# JTAG_Configuration.net
KiCad netlist of a schematic drawn in Altium Designer
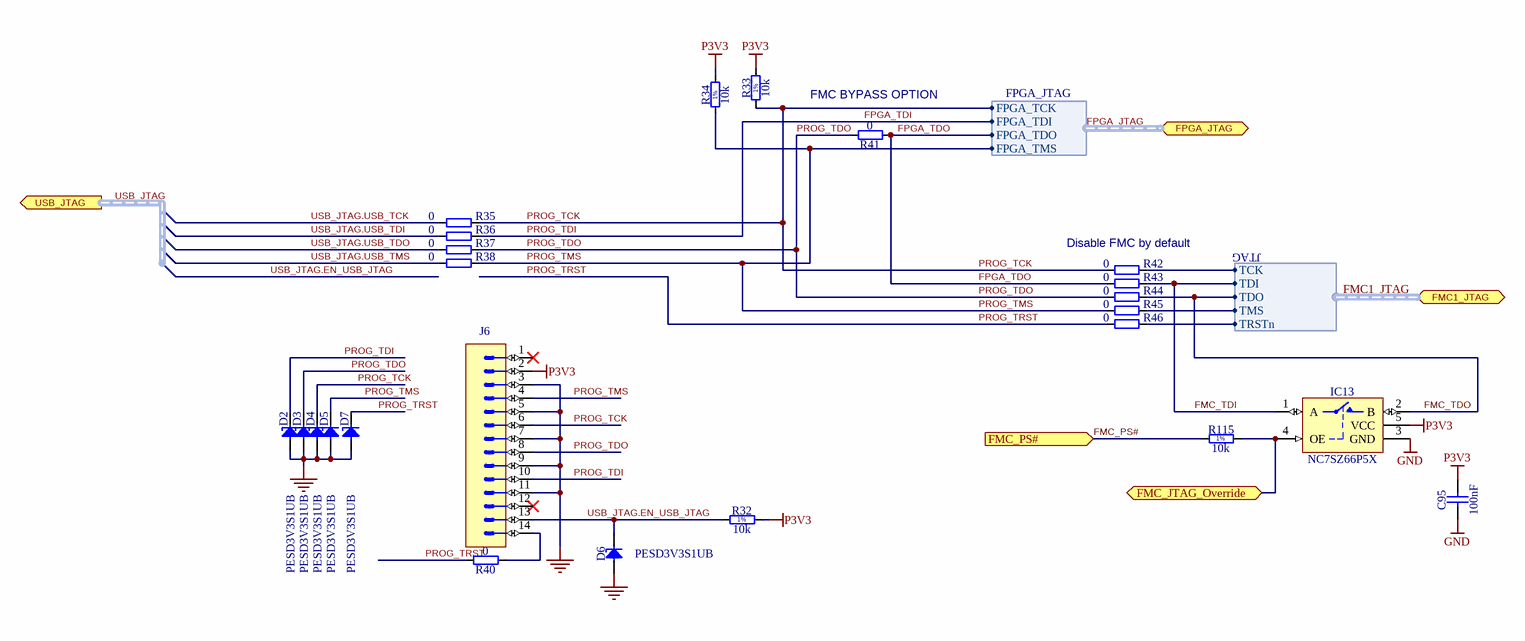
[diagram p0: JTAG_Configuration.SchDoc]

(export (version "E")
  (design (tool "Eeschema 10.0.6"))
  (components
    (comp (ref "C95")
      (value "100nF")
      (footprint "CAPC0603X33N")
      (description "Non-polarised capacitor")
      (fields
        (field (name "MANUFACTURER PART NUMBER") "CC0201_100NF_6.3V_10%_X5R")
        (field (name "MANUFACTURER") "GENERIC")
        (field (name "AUTHOR") "CERN DEM JLC")
      )
      (libsource (lib "Capacitors") (part "Capacitor - non polarized"))
    )
    (comp (ref "D2")
      (value "PESD3V3S1UB")
      (footprint "SODFL1608X65N")
      (description "ESD protection diode")
      (fields
        (field (name "MANUFACTURER") "NXP SEMICONDUCTORS")
        (field (name "VOLTAGE") "3V3")
        (field (name "AUTHOR") "CERN DEM JLC")
      )
      (libsource (lib "ICs And Semiconductors") (part "Diode ESD"))
    )
    (comp (ref "D3")
      (value "PESD3V3S1UB")
      (footprint "SODFL1608X65N")
      (description "ESD protection diode")
      (fields
        (field (name "MANUFACTURER") "NXP SEMICONDUCTORS")
        (field (name "VOLTAGE") "3V3")
        (field (name "AUTHOR") "CERN DEM JLC")
      )
      (libsource (lib "ICs And Semiconductors") (part "Diode ESD"))
    )
    (comp (ref "D4")
      (value "PESD3V3S1UB")
      (footprint "SODFL1608X65N")
      (description "ESD protection diode")
      (fields
        (field (name "MANUFACTURER") "NXP SEMICONDUCTORS")
        (field (name "VOLTAGE") "3V3")
        (field (name "AUTHOR") "CERN DEM JLC")
      )
      (libsource (lib "ICs And Semiconductors") (part "Diode ESD"))
    )
    (comp (ref "D5")
      (value "PESD3V3S1UB")
      (footprint "SODFL1608X65N")
      (description "ESD protection diode")
      (fields
        (field (name "MANUFACTURER") "NXP SEMICONDUCTORS")
        (field (name "VOLTAGE") "3V3")
        (field (name "AUTHOR") "CERN DEM JLC")
      )
      (libsource (lib "ICs And Semiconductors") (part "Diode ESD"))
    )
    (comp (ref "D6")
      (value "PESD3V3S1UB")
      (footprint "SODFL1608X65N")
      (description "ESD protection diode")
      (fields
        (field (name "MANUFACTURER") "NXP SEMICONDUCTORS")
        (field (name "VOLTAGE") "3V3")
        (field (name "AUTHOR") "CERN DEM JLC")
      )
      (libsource (lib "ICs And Semiconductors") (part "Diode ESD"))
    )
    (comp (ref "D7")
      (value "PESD3V3S1UB")
      (footprint "SODFL1608X65N")
      (description "ESD protection diode")
      (fields
        (field (name "MANUFACTURER") "NXP SEMICONDUCTORS")
        (field (name "VOLTAGE") "3V3")
        (field (name "AUTHOR") "CERN DEM JLC")
      )
      (libsource (lib "ICs And Semiconductors") (part "Diode ESD"))
    )
    (comp (ref "IC13")
      (value "NC7SZ66P5X")
      (footprint "SOT65P210X110-5N")
      (description "TinyLogic® Low Voltage Single SPST Normally Open Bus Switch")
      (fields (field (name "MANUFACTURER") "FAIRCHILD SEMICONDUCTOR") (field (name "AUTHOR") "CERN DEM JLC"))
      (libsource (lib "ICs And Semiconductors") (part "NC7SZ66P5X"))
    )
    (comp (ref "J6")
      (value "Milli-Grid™")
      (footprint "MOLEX_87832-1420")
      (description "Connector 14 Male")
      (fields
        (field (name "MANUFACTURER PART NUMBER") "87832-1420")
        (field (name "MANUFACTURER") "MOLEX")
        (field (name "AUTHOR") "CERN DEM JLC")
      )
      (libsource (lib "Connectors") (part "Connector 14 Male"))
    )
    (comp (ref "R32")
      (value "10k")
      (footprint "RESC1005X40N")
      (description "Resistor - 1%")
      (fields
        (field (name "MANUFACTURER PART NUMBER") "R0402_10K_1%_0.0625W_100PPM")
        (field (name "MANUFACTURER") "GENERIC")
        (field (name "AUTHOR") "CERN DEM JLC")
      )
      (libsource (lib "Resistors") (part "Resistor - 1%"))
    )
    (comp (ref "R33")
      (value "10k")
      (footprint "RESC1005X40N")
      (description "Resistor - 1%")
      (fields
        (field (name "MANUFACTURER PART NUMBER") "R0402_10K_1%_0.0625W_100PPM")
        (field (name "MANUFACTURER") "GENERIC")
        (field (name "AUTHOR") "CERN DEM JLC")
      )
      (libsource (lib "Resistors") (part "Resistor - 1%"))
    )
    (comp (ref "R34")
      (value "10k")
      (footprint "RESC1005X40N")
      (description "Resistor - 1%")
      (fields
        (field (name "MANUFACTURER PART NUMBER") "R0402_10K_1%_0.0625W_100PPM")
        (field (name "MANUFACTURER") "GENERIC")
        (field (name "AUTHOR") "CERN DEM JLC")
      )
      (libsource (lib "Resistors") (part "Resistor - 1%"))
    )
    (comp (ref "R35")
      (value "0")
      (footprint "RESC1005X40N")
      (description "Resistor")
      (fields
        (field (name "MANUFACTURER PART NUMBER") "R0402_0R_JUMPER")
        (field (name "MANUFACTURER") "GENERIC")
        (field (name "AUTHOR") "CERN DEM JLC")
      )
      (libsource (lib "Resistors") (part "Resistor"))
    )
    (comp (ref "R36")
      (value "0")
      (footprint "RESC1005X40N")
      (description "Resistor")
      (fields
        (field (name "MANUFACTURER PART NUMBER") "R0402_0R_JUMPER")
        (field (name "MANUFACTURER") "GENERIC")
        (field (name "AUTHOR") "CERN DEM JLC")
      )
      (libsource (lib "Resistors") (part "Resistor"))
    )
    (comp (ref "R37")
      (value "0")
      (footprint "RESC1005X40N")
      (description "Resistor")
      (fields
        (field (name "MANUFACTURER PART NUMBER") "R0402_0R_JUMPER")
        (field (name "MANUFACTURER") "GENERIC")
        (field (name "AUTHOR") "CERN DEM JLC")
      )
      (libsource (lib "Resistors") (part "Resistor"))
    )
    (comp (ref "R38")
      (value "0")
      (footprint "RESC1005X40N")
      (description "Resistor")
      (fields
        (field (name "MANUFACTURER PART NUMBER") "R0402_0R_JUMPER")
        (field (name "MANUFACTURER") "GENERIC")
        (field (name "AUTHOR") "CERN DEM JLC")
      )
      (libsource (lib "Resistors") (part "Resistor"))
    )
    (comp (ref "R40")
      (value "0")
      (footprint "RESC1005X40N")
      (description "Resistor")
      (fields
        (field (name "MANUFACTURER PART NUMBER") "R0402_0R_JUMPER")
        (field (name "MANUFACTURER") "GENERIC")
        (field (name "AUTHOR") "CERN DEM JLC")
      )
      (libsource (lib "Resistors") (part "Resistor"))
    )
    (comp (ref "R41")
      (value "0")
      (footprint "RESC1005X40N")
      (description "Resistor")
      (fields
        (field (name "MANUFACTURER PART NUMBER") "R0402_0R_JUMPER")
        (field (name "MANUFACTURER") "GENERIC")
        (field (name "AUTHOR") "CERN DEM JLC")
      )
      (libsource (lib "Resistors") (part "Resistor"))
    )
    (comp (ref "R42")
      (value "0")
      (footprint "RESC1005X40N")
      (description "Resistor")
      (fields
        (field (name "MANUFACTURER PART NUMBER") "R0402_0R_JUMPER")
        (field (name "MANUFACTURER") "GENERIC")
        (field (name "AUTHOR") "CERN DEM JLC")
      )
      (libsource (lib "Resistors") (part "Resistor"))
    )
    (comp (ref "R43")
      (value "0")
      (footprint "RESC1005X40N")
      (description "Resistor")
      (fields
        (field (name "MANUFACTURER PART NUMBER") "R0402_0R_JUMPER")
        (field (name "MANUFACTURER") "GENERIC")
        (field (name "AUTHOR") "CERN DEM JLC")
      )
      (libsource (lib "Resistors") (part "Resistor"))
    )
    (comp (ref "R44")
      (value "0")
      (footprint "RESC1005X40N")
      (description "Resistor")
      (fields
        (field (name "MANUFACTURER PART NUMBER") "R0402_0R_JUMPER")
        (field (name "MANUFACTURER") "GENERIC")
        (field (name "AUTHOR") "CERN DEM JLC")
      )
      (libsource (lib "Resistors") (part "Resistor"))
    )
    (comp (ref "R45")
      (value "0")
      (footprint "RESC1005X40N")
      (description "Resistor")
      (fields
        (field (name "MANUFACTURER PART NUMBER") "R0402_0R_JUMPER")
        (field (name "MANUFACTURER") "GENERIC")
        (field (name "AUTHOR") "CERN DEM JLC")
      )
      (libsource (lib "Resistors") (part "Resistor"))
    )
    (comp (ref "R46")
      (value "0")
      (footprint "RESC1005X40N")
      (description "Resistor")
      (fields
        (field (name "MANUFACTURER PART NUMBER") "R0402_0R_JUMPER")
        (field (name "MANUFACTURER") "GENERIC")
        (field (name "AUTHOR") "CERN DEM JLC")
      )
      (libsource (lib "Resistors") (part "Resistor"))
    )
    (comp (ref "R115")
      (value "10k")
      (footprint "RESC1005X40N")
      (description "Resistor - 1%")
      (fields
        (field (name "MANUFACTURER PART NUMBER") "R0402_10K_1%_0.0625W_100PPM")
        (field (name "MANUFACTURER") "GENERIC")
        (field (name "AUTHOR") "CERN DEM JLC")
      )
      (libsource (lib "Resistors") (part "Resistor - 1%"))
    )
  )
  (nets
    (net (code "5") (name "/FMC_JTAG_Override") (class "Default")
      (node (ref "IC13") (pin "4") (pinfunction "OE_4") (pintype "input"))
      (node (ref "R115") (pin "2") (pinfunction "2_2") (pintype "passive"))
    )
    (net (code "6") (name "/FMC_PS#") (class "Default")
      (node (ref "R115") (pin "1") (pinfunction "1_1") (pintype "passive"))
    )
    (net (code "7") (name "/FMC_TDI") (class "Default")
      (node (ref "IC13") (pin "1") (pinfunction "A_1") (pintype "bidirectional"))
      (node (ref "R43") (pin "1") (pinfunction "1_1") (pintype "passive"))
    )
    (net (code "8") (name "/FMC_TDO") (class "Default")
      (node (ref "IC13") (pin "2") (pinfunction "B_2") (pintype "bidirectional"))
      (node (ref "R44") (pin "1") (pinfunction "1_1") (pintype "passive"))
    )
    (net (code "10") (name "/FPGA_TDI") (class "Default")
      (node (ref "D2") (pin "1") (pinfunction "C_1") (pintype "passive"))
      (node (ref "J6") (pin "10") (pinfunction "10_10") (pintype "bidirectional"))
      (node (ref "R36") (pin "1") (pinfunction "1_1") (pintype "passive"))
    )
    (net (code "11") (name "/FPGA_TDO") (class "Default")
      (node (ref "R41") (pin "1") (pinfunction "1_1") (pintype "passive"))
      (node (ref "R43") (pin "2") (pinfunction "2_2") (pintype "passive"))
    )
    (net (code "12") (name "/PROG_TCK") (class "Default")
      (node (ref "D4") (pin "1") (pinfunction "C_1") (pintype "passive"))
      (node (ref "J6") (pin "6") (pinfunction "6_6") (pintype "bidirectional"))
      (node (ref "R33") (pin "1") (pinfunction "1_1") (pintype "passive"))
      (node (ref "R35") (pin "1") (pinfunction "1_1") (pintype "passive"))
      (node (ref "R42") (pin "2") (pinfunction "2_2") (pintype "passive"))
    )
    (net (code "13") (name "/PROG_TDO") (class "Default")
      (node (ref "D3") (pin "1") (pinfunction "C_1") (pintype "passive"))
      (node (ref "J6") (pin "8") (pinfunction "8_8") (pintype "bidirectional"))
      (node (ref "R37") (pin "1") (pinfunction "1_1") (pintype "passive"))
      (node (ref "R41") (pin "2") (pinfunction "2_2") (pintype "passive"))
      (node (ref "R44") (pin "2") (pinfunction "2_2") (pintype "passive"))
    )
    (net (code "14") (name "/PROG_TMS") (class "Default")
      (node (ref "D5") (pin "1") (pinfunction "C_1") (pintype "passive"))
      (node (ref "J6") (pin "4") (pinfunction "4_4") (pintype "bidirectional"))
      (node (ref "R34") (pin "1") (pinfunction "1_1") (pintype "passive"))
      (node (ref "R38") (pin "1") (pinfunction "1_1") (pintype "passive"))
      (node (ref "R45") (pin "2") (pinfunction "2_2") (pintype "passive"))
    )
    (net (code "15") (name "/PROG_TRST") (class "Default")
      (node (ref "D7") (pin "1") (pinfunction "C_1") (pintype "passive"))
      (node (ref "R40") (pin "2") (pinfunction "2_2") (pintype "passive"))
      (node (ref "R46") (pin "2") (pinfunction "2_2") (pintype "passive"))
    )
    (net (code "16") (name "/TCK") (class "Default")
      (node (ref "R42") (pin "1") (pinfunction "1_1") (pintype "passive"))
    )
    (net (code "17") (name "/TMS") (class "Default")
      (node (ref "R45") (pin "1") (pinfunction "1_1") (pintype "passive"))
    )
    (net (code "18") (name "/TRSTn") (class "Default")
      (node (ref "R46") (pin "1") (pinfunction "1_1") (pintype "passive"))
    )
    (net (code "19") (name "/USB_JTAG.EN_USB_JTAG") (class "Default")
      (node (ref "D6") (pin "1") (pinfunction "C_1") (pintype "passive"))
      (node (ref "J6") (pin "13") (pinfunction "13_13") (pintype "bidirectional"))
      (node (ref "R32") (pin "1") (pinfunction "1_1") (pintype "passive"))
    )
    (net (code "20") (name "/USB_JTAG.USB_TCK") (class "Default")
      (node (ref "R35") (pin "2") (pinfunction "2_2") (pintype "passive"))
    )
    (net (code "21") (name "/USB_JTAG.USB_TDI") (class "Default")
      (node (ref "R36") (pin "2") (pinfunction "2_2") (pintype "passive"))
    )
    (net (code "22") (name "/USB_JTAG.USB_TDO") (class "Default")
      (node (ref "R37") (pin "2") (pinfunction "2_2") (pintype "passive"))
    )
    (net (code "23") (name "/USB_JTAG.USB_TMS") (class "Default")
      (node (ref "R38") (pin "2") (pinfunction "2_2") (pintype "passive"))
    )
    (net (code "25") (name "GND") (class "Default")
      (node (ref "C95") (pin "1") (pinfunction "1_1") (pintype "passive"))
      (node (ref "D2") (pin "2") (pinfunction "A_2") (pintype "passive"))
      (node (ref "D3") (pin "2") (pinfunction "A_2") (pintype "passive"))
      (node (ref "D4") (pin "2") (pinfunction "A_2") (pintype "passive"))
      (node (ref "D5") (pin "2") (pinfunction "A_2") (pintype "passive"))
      (node (ref "D6") (pin "2") (pinfunction "A_2") (pintype "passive"))
      (node (ref "D7") (pin "2") (pinfunction "A_2") (pintype "passive"))
      (node (ref "IC13") (pin "3") (pinfunction "GND_3") (pintype "power_in"))
      (node (ref "J6") (pin "11") (pinfunction "11_11") (pintype "bidirectional"))
      (node (ref "J6") (pin "3") (pinfunction "3_3") (pintype "bidirectional"))
      (node (ref "J6") (pin "5") (pinfunction "5_5") (pintype "bidirectional"))
      (node (ref "J6") (pin "7") (pinfunction "7_7") (pintype "bidirectional"))
      (node (ref "J6") (pin "9") (pinfunction "9_9") (pintype "bidirectional"))
    )
    (net (code "26") (name "Net-(J6-Pad14)") (class "Default")
      (node (ref "J6") (pin "14") (pinfunction "14_14") (pintype "bidirectional"))
      (node (ref "R40") (pin "1") (pinfunction "1_1") (pintype "passive"))
    )
    (net (code "27") (name "P3V3") (class "Default")
      (node (ref "C95") (pin "2") (pinfunction "2_2") (pintype "passive"))
      (node (ref "IC13") (pin "5") (pinfunction "VCC_5") (pintype "power_in"))
      (node (ref "J6") (pin "2") (pinfunction "2_2") (pintype "bidirectional"))
      (node (ref "R32") (pin "2") (pinfunction "2_2") (pintype "passive"))
      (node (ref "R33") (pin "2") (pinfunction "2_2") (pintype "passive"))
      (node (ref "R34") (pin "2") (pinfunction "2_2") (pintype "passive"))
    )
    (net (code "28") (name "unconnected-(J6-Pad1)") (class "Default")
      (node (ref "J6") (pin "1") (pinfunction "1_1") (pintype "bidirectional+no_connect"))
    )
    (net (code "29") (name "unconnected-(J6-Pad12)") (class "Default")
      (node (ref "J6") (pin "12") (pinfunction "12_12") (pintype "bidirectional+no_connect"))
    )
  )
)
